# AVR_ProgrammingBoard.net
KiCad netlist of a schematic drawn in EAGLE
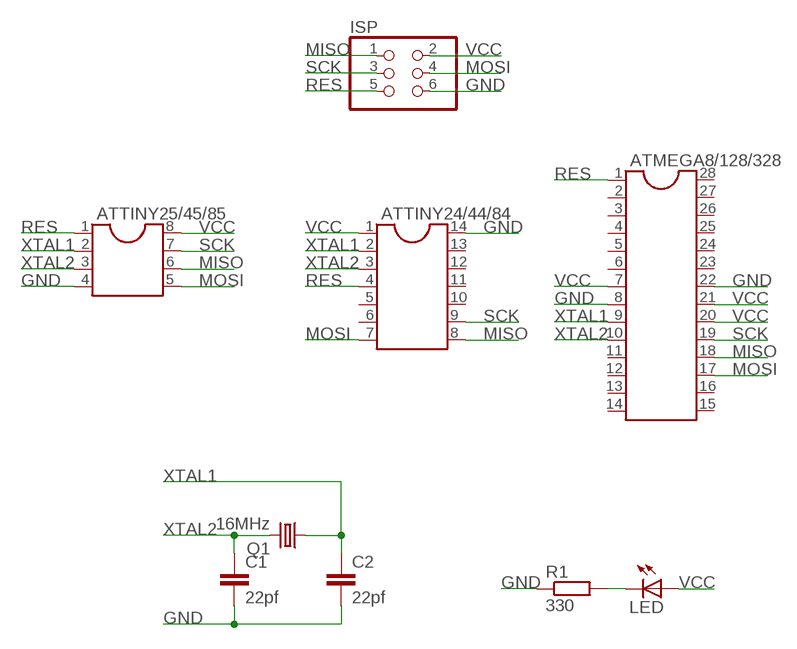
[diagram p0: schematic, sheet 1]

(export (version "E")
  (design (tool "Eeschema 10.0.6"))
  (components
    (comp (ref "ATMEGA8/128/328")
      (value "DIL28-3")
      (footprint "eagle-import:DIL28-3")
      (libsource (lib "eagle-import") (part "DIL28-3"))
    )
    (comp (ref "ATTINY24/44/84")
      (value "DIL14")
      (footprint "eagle-import:DIL14")
      (libsource (lib "eagle-import") (part "DIL14"))
    )
    (comp (ref "ATTINY25/45/85")
      (value "DIL8")
      (footprint "eagle-import:DIL08")
      (libsource (lib "eagle-import") (part "DIL8"))
    )
    (comp (ref "C1")
      (value "22pf")
      (footprint "eagle-import:C5B3")
      (libsource (lib "eagle-import") (part "C5/3"))
    )
    (comp (ref "C2")
      (value "22pf")
      (footprint "eagle-import:C5B3")
      (libsource (lib "eagle-import") (part "C5/3"))
    )
    (comp (ref "ISP")
      (value "PINHD-2X3")
      (footprint "eagle-import:2X03")
      (libsource (lib "eagle-import") (part "PINHD-2X3"))
    )
    (comp (ref "LED")
      (value "LED5MM")
      (footprint "eagle-import:LED5MM")
      (libsource (lib "eagle-import") (part "LED5MM"))
    )
    (comp (ref "Q1")
      (value "16MHz")
      (footprint "eagle-import:HC49U-V")
      (libsource (lib "eagle-import") (part "CRYSTALHC49U-V"))
    )
    (comp (ref "R1")
      (value "330")
      (footprint "eagle-import:0204_7")
      (libsource (lib "eagle-import") (part "R-EU_0204/7"))
    )
  )
  (nets
    (net (code "1") (name "/GND") (class "Default")
      (node (ref "ATMEGA8/128/328") (pin "22") (pinfunction "22_22") (pintype "passive"))
      (node (ref "ATMEGA8/128/328") (pin "8") (pinfunction "8_8") (pintype "passive"))
      (node (ref "ATTINY24/44/84") (pin "14") (pinfunction "14_14") (pintype "passive"))
      (node (ref "ATTINY25/45/85") (pin "4") (pinfunction "4_4") (pintype "passive"))
      (node (ref "C1") (pin "2") (pinfunction "2_2") (pintype "passive"))
      (node (ref "C2") (pin "2") (pinfunction "2_2") (pintype "passive"))
      (node (ref "ISP") (pin "6") (pinfunction "6_6") (pintype "passive"))
      (node (ref "R1") (pin "1") (pinfunction "1_1") (pintype "passive"))
    )
    (net (code "2") (name "/MISO") (class "Default")
      (node (ref "ATMEGA8/128/328") (pin "18") (pinfunction "18_18") (pintype "passive"))
      (node (ref "ATTINY24/44/84") (pin "8") (pinfunction "8_8") (pintype "passive"))
      (node (ref "ATTINY25/45/85") (pin "6") (pinfunction "6_6") (pintype "passive"))
      (node (ref "ISP") (pin "1") (pinfunction "1_1") (pintype "passive"))
    )
    (net (code "3") (name "/MOSI") (class "Default")
      (node (ref "ATMEGA8/128/328") (pin "17") (pinfunction "17_17") (pintype "passive"))
      (node (ref "ATTINY24/44/84") (pin "7") (pinfunction "7_7") (pintype "passive"))
      (node (ref "ATTINY25/45/85") (pin "5") (pinfunction "5_5") (pintype "passive"))
      (node (ref "ISP") (pin "4") (pinfunction "4_4") (pintype "passive"))
    )
    (net (code "4") (name "/RES") (class "Default")
      (node (ref "ATMEGA8/128/328") (pin "1") (pinfunction "1_1") (pintype "passive"))
      (node (ref "ATTINY24/44/84") (pin "4") (pinfunction "4_4") (pintype "passive"))
      (node (ref "ATTINY25/45/85") (pin "1") (pinfunction "1_1") (pintype "passive"))
      (node (ref "ISP") (pin "5") (pinfunction "5_5") (pintype "passive"))
    )
    (net (code "5") (name "/SCK") (class "Default")
      (node (ref "ATMEGA8/128/328") (pin "19") (pinfunction "19_19") (pintype "passive"))
      (node (ref "ATTINY24/44/84") (pin "9") (pinfunction "9_9") (pintype "passive"))
      (node (ref "ATTINY25/45/85") (pin "7") (pinfunction "7_7") (pintype "passive"))
      (node (ref "ISP") (pin "3") (pinfunction "3_3") (pintype "passive"))
    )
    (net (code "6") (name "/VCC") (class "Default")
      (node (ref "ATMEGA8/128/328") (pin "20") (pinfunction "20_20") (pintype "passive"))
      (node (ref "ATMEGA8/128/328") (pin "21") (pinfunction "21_21") (pintype "passive"))
      (node (ref "ATMEGA8/128/328") (pin "7") (pinfunction "7_7") (pintype "passive"))
      (node (ref "ATTINY24/44/84") (pin "1") (pinfunction "1_1") (pintype "passive"))
      (node (ref "ATTINY25/45/85") (pin "8") (pinfunction "8_8") (pintype "passive"))
      (node (ref "ISP") (pin "2") (pinfunction "2_2") (pintype "passive"))
      (node (ref "LED") (pin "A") (pinfunction "A_A") (pintype "passive"))
    )
    (net (code "7") (name "/XTAL1") (class "Default")
      (node (ref "ATMEGA8/128/328") (pin "9") (pinfunction "9_9") (pintype "passive"))
      (node (ref "ATTINY24/44/84") (pin "2") (pinfunction "2_2") (pintype "passive"))
      (node (ref "ATTINY25/45/85") (pin "2") (pinfunction "2_2") (pintype "passive"))
      (node (ref "C2") (pin "1") (pinfunction "1_1") (pintype "passive"))
      (node (ref "Q1") (pin "1") (pinfunction "1_1") (pintype "passive"))
    )
    (net (code "8") (name "/XTAL2") (class "Default")
      (node (ref "ATMEGA8/128/328") (pin "10") (pinfunction "10_10") (pintype "passive"))
      (node (ref "ATTINY24/44/84") (pin "3") (pinfunction "3_3") (pintype "passive"))
      (node (ref "ATTINY25/45/85") (pin "3") (pinfunction "3_3") (pintype "passive"))
      (node (ref "C1") (pin "1") (pinfunction "1_1") (pintype "passive"))
      (node (ref "Q1") (pin "2") (pinfunction "2_2") (pintype "passive"))
    )
    (net (code "9") (name "Net-(LED-C)") (class "Default")
      (node (ref "LED") (pin "K") (pinfunction "C_K") (pintype "passive"))
      (node (ref "R1") (pin "2") (pinfunction "2_2") (pintype "passive"))
    )
    (net (code "10") (name "unconnected-(ATMEGA8/128/328-Pad2)") (class "Default")
      (node (ref "ATMEGA8/128/328") (pin "2") (pinfunction "2_2") (pintype "passive"))
    )
    (net (code "11") (name "unconnected-(ATMEGA8/128/328-Pad3)") (class "Default")
      (node (ref "ATMEGA8/128/328") (pin "3") (pinfunction "3_3") (pintype "passive"))
    )
    (net (code "12") (name "unconnected-(ATMEGA8/128/328-Pad4)") (class "Default")
      (node (ref "ATMEGA8/128/328") (pin "4") (pinfunction "4_4") (pintype "passive"))
    )
    (net (code "13") (name "unconnected-(ATMEGA8/128/328-Pad5)") (class "Default")
      (node (ref "ATMEGA8/128/328") (pin "5") (pinfunction "5_5") (pintype "passive"))
    )
    (net (code "14") (name "unconnected-(ATMEGA8/128/328-Pad6)") (class "Default")
      (node (ref "ATMEGA8/128/328") (pin "6") (pinfunction "6_6") (pintype "passive"))
    )
    (net (code "15") (name "unconnected-(ATMEGA8/128/328-Pad11)") (class "Default")
      (node (ref "ATMEGA8/128/328") (pin "11") (pinfunction "11_11") (pintype "passive"))
    )
    (net (code "16") (name "unconnected-(ATMEGA8/128/328-Pad12)") (class "Default")
      (node (ref "ATMEGA8/128/328") (pin "12") (pinfunction "12_12") (pintype "passive"))
    )
    (net (code "17") (name "unconnected-(ATMEGA8/128/328-Pad13)") (class "Default")
      (node (ref "ATMEGA8/128/328") (pin "13") (pinfunction "13_13") (pintype "passive"))
    )
    (net (code "18") (name "unconnected-(ATMEGA8/128/328-Pad14)") (class "Default")
      (node (ref "ATMEGA8/128/328") (pin "14") (pinfunction "14_14") (pintype "passive"))
    )
    (net (code "19") (name "unconnected-(ATMEGA8/128/328-Pad15)") (class "Default")
      (node (ref "ATMEGA8/128/328") (pin "15") (pinfunction "15_15") (pintype "passive"))
    )
    (net (code "20") (name "unconnected-(ATMEGA8/128/328-Pad16)") (class "Default")
      (node (ref "ATMEGA8/128/328") (pin "16") (pinfunction "16_16") (pintype "passive"))
    )
    (net (code "21") (name "unconnected-(ATMEGA8/128/328-Pad23)") (class "Default")
      (node (ref "ATMEGA8/128/328") (pin "23") (pinfunction "23_23") (pintype "passive"))
    )
    (net (code "22") (name "unconnected-(ATMEGA8/128/328-Pad24)") (class "Default")
      (node (ref "ATMEGA8/128/328") (pin "24") (pinfunction "24_24") (pintype "passive"))
    )
    (net (code "23") (name "unconnected-(ATMEGA8/128/328-Pad25)") (class "Default")
      (node (ref "ATMEGA8/128/328") (pin "25") (pinfunction "25_25") (pintype "passive"))
    )
    (net (code "24") (name "unconnected-(ATMEGA8/128/328-Pad26)") (class "Default")
      (node (ref "ATMEGA8/128/328") (pin "26") (pinfunction "26_26") (pintype "passive"))
    )
    (net (code "25") (name "unconnected-(ATMEGA8/128/328-Pad27)") (class "Default")
      (node (ref "ATMEGA8/128/328") (pin "27") (pinfunction "27_27") (pintype "passive"))
    )
    (net (code "26") (name "unconnected-(ATMEGA8/128/328-Pad28)") (class "Default")
      (node (ref "ATMEGA8/128/328") (pin "28") (pinfunction "28_28") (pintype "passive"))
    )
    (net (code "27") (name "unconnected-(ATTINY24/44/84-Pad5)") (class "Default")
      (node (ref "ATTINY24/44/84") (pin "5") (pinfunction "5_5") (pintype "passive"))
    )
    (net (code "28") (name "unconnected-(ATTINY24/44/84-Pad6)") (class "Default")
      (node (ref "ATTINY24/44/84") (pin "6") (pinfunction "6_6") (pintype "passive"))
    )
    (net (code "29") (name "unconnected-(ATTINY24/44/84-Pad10)") (class "Default")
      (node (ref "ATTINY24/44/84") (pin "10") (pinfunction "10_10") (pintype "passive"))
    )
    (net (code "30") (name "unconnected-(ATTINY24/44/84-Pad11)") (class "Default")
      (node (ref "ATTINY24/44/84") (pin "11") (pinfunction "11_11") (pintype "passive"))
    )
    (net (code "31") (name "unconnected-(ATTINY24/44/84-Pad12)") (class "Default")
      (node (ref "ATTINY24/44/84") (pin "12") (pinfunction "12_12") (pintype "passive"))
    )
    (net (code "32") (name "unconnected-(ATTINY24/44/84-Pad13)") (class "Default")
      (node (ref "ATTINY24/44/84") (pin "13") (pinfunction "13_13") (pintype "passive"))
    )
  )
)
